# sqrwear2_0.net
KiCad netlist of a schematic drawn in EAGLE
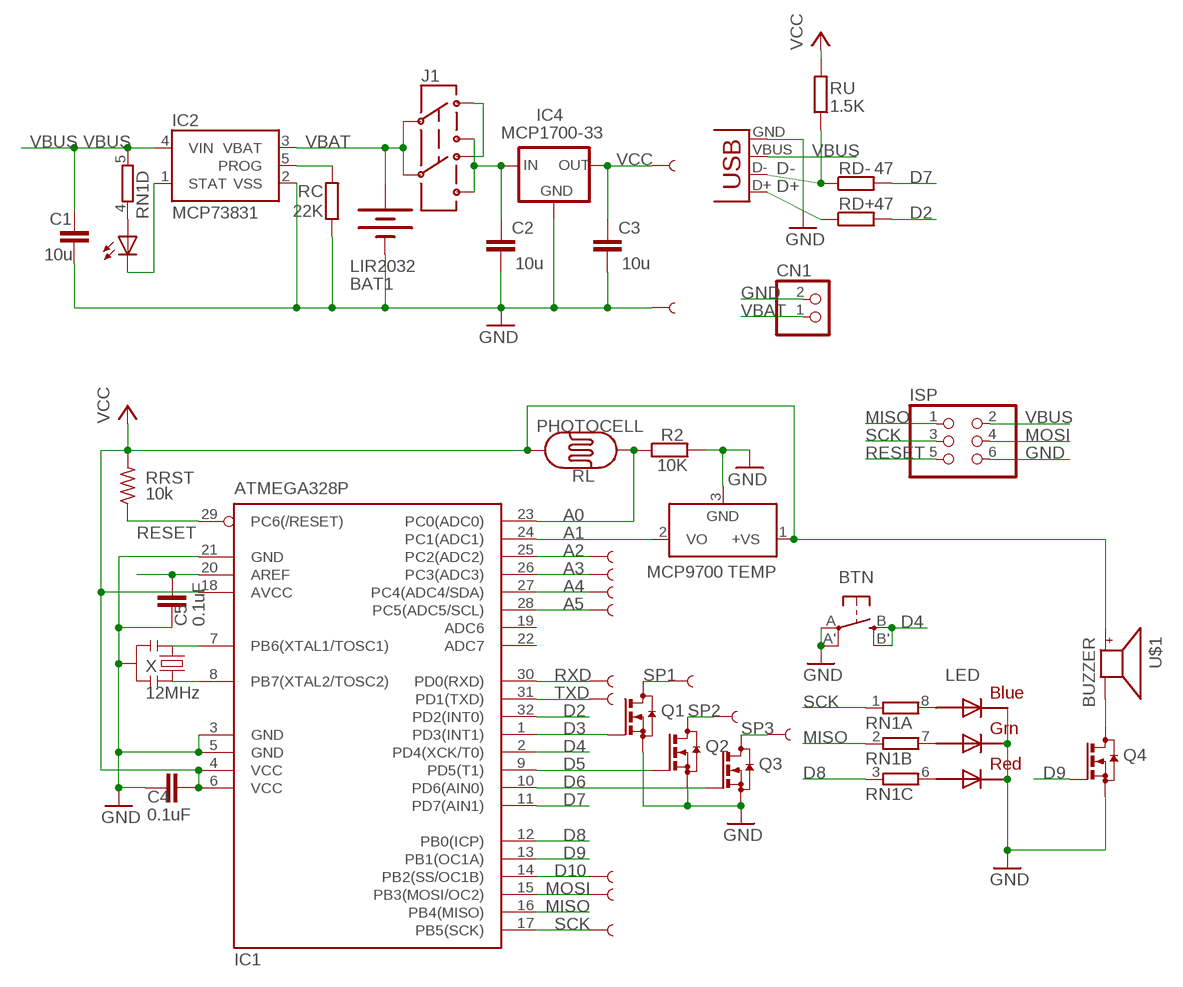
[diagram p0: schematic, sheet 1]

(export (version "E")
  (design (tool "Eeschema 10.0.6"))
  (components
    (comp (ref "BAT1")
      (value "LIR2032")
      (footprint "eagle-import:BATTCOM_20MM_PTH_SMT")
      (libsource (lib "eagle-import") (part "BATTERYBATTCOM_20MM_PTH_SMT"))
    )
    (comp (ref "BTN")
      (value "EVQQ2")
      (footprint "eagle-import:EVQ-Q2")
      (libsource (lib "eagle-import") (part "EVQQ2"))
    )
    (comp (ref "C1")
      (value "10u")
      (footprint "eagle-import:C0805")
      (libsource (lib "eagle-import") (part "resistor_C-EUC0805"))
    )
    (comp (ref "C2")
      (value "10u")
      (footprint "eagle-import:C0805")
      (libsource (lib "eagle-import") (part "resistor_C-EUC0805"))
    )
    (comp (ref "C3")
      (value "10u")
      (footprint "eagle-import:C0805")
      (libsource (lib "eagle-import") (part "resistor_C-EUC0805"))
    )
    (comp (ref "C4")
      (value "0.1uF")
      (footprint "eagle-import:C0805")
      (libsource (lib "eagle-import") (part "C-EUC0805"))
    )
    (comp (ref "C5")
      (value "0.1uF")
      (footprint "eagle-import:C0805")
      (libsource (lib "eagle-import") (part "C-EUC0805"))
    )
    (comp (ref "CHG")
      (value "0805")
      (footprint "eagle-import:CHIPLED_0805")
      (libsource (lib "eagle-import") (part "LEDCHIPLED_0805"))
    )
    (comp (ref "CN1")
      (value "JST_2PIN-SMT-RA")
      (footprint "eagle-import:JST-PH-2-SMT-RA")
      (libsource (lib "eagle-import") (part "JST_2PIN-SMT-RA"))
    )
    (comp (ref "IC1")
      (value "ATMEGA328P")
      (footprint "eagle-import:TQFP32-08")
      (fields (field (name "MPN") "ATMEGA8-16AU"))
      (libsource (lib "eagle-import") (part "MEGA8-AI"))
    )
    (comp (ref "IC2")
      (value "MCP73831")
      (footprint "eagle-import:SOT23-5")
      (libsource (lib "eagle-import") (part "MCP73831"))
    )
    (comp (ref "IC4")
      (value "MCP1700-33")
      (footprint "eagle-import:SOT23")
      (libsource (lib "eagle-import") (part "MCP1700SOT233"))
    )
    (comp (ref "ISP")
      (value "PINHD-2X3")
      (footprint "eagle-import:2X03")
      (libsource (lib "eagle-import") (part "PINHD-2X3"))
    )
    (comp (ref "J1")
      (value "AYZ0202")
      (footprint "eagle-import:AYZ0202")
      (libsource (lib "eagle-import") (part "AYZ0202"))
    )
    (comp (ref "LED")
      (value "RGBLED5050")
      (footprint "eagle-import:RGBLED5050")
      (libsource (lib "eagle-import") (part "RGBLED5050"))
    )
    (comp (ref "PAD_3")
      (value "SEWTAP6")
      (footprint "eagle-import:PETAL-SMALL-2SIDE11")
      (libsource (lib "eagle-import") (part "SEWTAP611"))
    )
    (comp (ref "PAD_5")
      (value "SEWTAP6")
      (footprint "eagle-import:PETAL-SMALL-2SIDE1")
      (libsource (lib "eagle-import") (part "SEWTAP61"))
    )
    (comp (ref "PAD_6")
      (value "SEWTAP6")
      (footprint "eagle-import:PETAL-SMALL-2SIDE1")
      (libsource (lib "eagle-import") (part "SEWTAP61"))
    )
    (comp (ref "PAD_10")
      (value "SEWTAP6")
      (footprint "eagle-import:PETAL-SMALL-2SIDE11")
      (libsource (lib "eagle-import") (part "SEWTAP611"))
    )
    (comp (ref "PAD_11")
      (value "SEWTAP6")
      (footprint "eagle-import:PETAL-SMALL-2SIDE1")
      (libsource (lib "eagle-import") (part "SEWTAP61"))
    )
    (comp (ref "PAD_13")
      (value "SEWTAP6")
      (footprint "eagle-import:PETAL-SMALL-2SIDE1")
      (libsource (lib "eagle-import") (part "SEWTAP61"))
    )
    (comp (ref "PAD_A2")
      (value "SEWTAP6")
      (footprint "eagle-import:PETAL-SMALL-2SIDE1")
      (libsource (lib "eagle-import") (part "SEWTAP61"))
    )
    (comp (ref "PAD_A3")
      (value "SEWTAP6")
      (footprint "eagle-import:PETAL-SMALL-2SIDE1")
      (libsource (lib "eagle-import") (part "SEWTAP61"))
    )
    (comp (ref "PAD_A4")
      (value "SEWTAP6")
      (footprint "eagle-import:PETAL-SMALL-2SIDE11")
      (libsource (lib "eagle-import") (part "SEWTAP611"))
    )
    (comp (ref "PAD_A5")
      (value "SEWTAP6")
      (footprint "eagle-import:PETAL-SMALL-2SIDE11")
      (libsource (lib "eagle-import") (part "SEWTAP611"))
    )
    (comp (ref "PAD_GND")
      (value "SEWTAP6")
      (footprint "eagle-import:PETAL-SMALL-2SIDE11")
      (libsource (lib "eagle-import") (part "SEWTAP611"))
    )
    (comp (ref "PAD_RXD")
      (value "SEWTAP61")
      (footprint "eagle-import:PETAL-SMALL-2SIDE1")
      (libsource (lib "eagle-import") (part "SEWTAP61"))
    )
    (comp (ref "PAD_TXD")
      (value "SEWTAP6")
      (footprint "eagle-import:PETAL-SMALL-2SIDE1")
      (libsource (lib "eagle-import") (part "SEWTAP61"))
    )
    (comp (ref "PAD_VCC")
      (value "SEWTAP6")
      (footprint "eagle-import:PETAL-SMALL-2SIDE11")
      (libsource (lib "eagle-import") (part "SEWTAP611"))
    )
    (comp (ref "Q1")
      (value "BSS123")
      (footprint "eagle-import:SOT23")
      (libsource (lib "eagle-import") (part "BSS123"))
    )
    (comp (ref "Q2")
      (value "BSS123")
      (footprint "eagle-import:SOT23")
      (libsource (lib "eagle-import") (part "BSS123"))
    )
    (comp (ref "Q3")
      (value "BSS123")
      (footprint "eagle-import:SOT23")
      (libsource (lib "eagle-import") (part "BSS123"))
    )
    (comp (ref "Q4")
      (value "BSS123")
      (footprint "eagle-import:SOT23")
      (libsource (lib "eagle-import") (part "BSS123"))
    )
    (comp (ref "R2")
      (value "10K")
      (footprint "eagle-import:R0805")
      (libsource (lib "eagle-import") (part "R-EU_R0805"))
    )
    (comp (ref "RC")
      (value "22K")
      (footprint "eagle-import:R0805")
      (libsource (lib "eagle-import") (part "R-EU_R0805"))
    )
    (comp (ref "RD+")
      (value "47")
      (footprint "eagle-import:R0805")
      (libsource (lib "eagle-import") (part "R-EU_R0805"))
    )
    (comp (ref "RD-")
      (value "47")
      (footprint "eagle-import:R0805")
      (libsource (lib "eagle-import") (part "R-EU_R0805"))
    )
    (comp (ref "RL")
      (value "PHOTOCELL")
      (footprint "eagle-import:PHOTOCELL")
      (libsource (lib "eagle-import") (part "PHOTOCELLPTH"))
    )
    (comp (ref "RN1")
      (value "4R-NEXB38V")
      (footprint "eagle-import:EXB38V")
      (libsource (lib "eagle-import") (part "4R-NEXB38V"))
    )
    (comp (ref "RRST")
      (value "10k")
      (footprint "eagle-import:R0805@1")
      (libsource (lib "eagle-import") (part "R-US_R0805"))
    )
    (comp (ref "RU")
      (value "1.5K")
      (footprint "eagle-import:R0805")
      (libsource (lib "eagle-import") (part "R-EU_R0805"))
    )
    (comp (ref "TEMP")
      (value "MCP9700")
      (footprint "eagle-import:SOT23")
      (libsource (lib "eagle-import") (part "LM50"))
    )
    (comp (ref "U$1")
      (value "BUZZER")
      (footprint "eagle-import:SMT-8585-BUZZER")
      (libsource (lib "eagle-import") (part "BUZZER"))
    )
    (comp (ref "X")
      (value "12MHz")
      (footprint "eagle-import:RESONATOR-SMD")
      (libsource (lib "eagle-import") (part "RESONATORSMD"))
    )
    (comp (ref "X1")
      (value "USBSMD")
      (footprint "eagle-import:USB-MINIB")
      (libsource (lib "eagle-import") (part "USBSMD"))
    )
  )
  (nets
    (net (code "1") (name "/A0") (class "Default")
      (node (ref "IC1") (pin "23") (pinfunction "PC0(ADC0)_23") (pintype "bidirectional"))
      (node (ref "R2") (pin "1") (pinfunction "1_1") (pintype "passive"))
      (node (ref "RL") (pin "1") (pinfunction "P$1_1") (pintype "bidirectional"))
    )
    (net (code "2") (name "/A1") (class "Default")
      (node (ref "IC1") (pin "24") (pinfunction "PC1(ADC1)_24") (pintype "bidirectional"))
      (node (ref "TEMP") (pin "2") (pinfunction "VO_2") (pintype "input"))
    )
    (net (code "3") (name "/A2") (class "Default")
      (node (ref "IC1") (pin "25") (pinfunction "PC2(ADC2)_25") (pintype "bidirectional"))
      (node (ref "PAD_A2") (pin "1") (pinfunction "1_1") (pintype "bidirectional"))
    )
    (net (code "4") (name "/A3") (class "Default")
      (node (ref "IC1") (pin "26") (pinfunction "PC3(ADC3)_26") (pintype "bidirectional"))
      (node (ref "PAD_A3") (pin "1") (pinfunction "1_1") (pintype "bidirectional"))
    )
    (net (code "5") (name "/A4") (class "Default")
      (node (ref "IC1") (pin "27") (pinfunction "PC4(ADC4/SDA)_27") (pintype "bidirectional"))
      (node (ref "PAD_A4") (pin "1") (pinfunction "1_1") (pintype "bidirectional"))
    )
    (net (code "6") (name "/A5") (class "Default")
      (node (ref "IC1") (pin "28") (pinfunction "PC5(ADC5/SCL)_28") (pintype "bidirectional"))
      (node (ref "PAD_A5") (pin "1") (pinfunction "1_1") (pintype "bidirectional"))
    )
    (net (code "7") (name "/D+") (class "Default")
      (node (ref "RD+") (pin "1") (pinfunction "1_1") (pintype "passive"))
      (node (ref "X1") (pin "D+") (pinfunction "D+_D+") (pintype "bidirectional"))
    )
    (net (code "8") (name "/D-") (class "Default")
      (node (ref "RD-") (pin "1") (pinfunction "1_1") (pintype "passive"))
      (node (ref "RU") (pin "1") (pinfunction "1_1") (pintype "passive"))
      (node (ref "X1") (pin "D-") (pinfunction "D-_D-") (pintype "bidirectional"))
    )
    (net (code "9") (name "/D2") (class "Default")
      (node (ref "IC1") (pin "32") (pinfunction "PD2(INT0)_32") (pintype "bidirectional"))
      (node (ref "RD+") (pin "2") (pinfunction "2_2") (pintype "passive"))
    )
    (net (code "10") (name "/D3") (class "Default")
      (node (ref "IC1") (pin "1") (pinfunction "PD3(INT1)_1") (pintype "bidirectional"))
      (node (ref "Q1") (pin "1") (pinfunction "G_1") (pintype "passive"))
    )
    (net (code "11") (name "/D4") (class "Default")
      (node (ref "BTN") (pin "B") (pinfunction "S_B") (pintype "passive"))
      (node (ref "BTN") (pin "B'") (pinfunction "S1_B'") (pintype "passive"))
      (node (ref "IC1") (pin "2") (pinfunction "PD4(XCK/T0)_2") (pintype "bidirectional"))
    )
    (net (code "12") (name "/D5") (class "Default")
      (node (ref "IC1") (pin "9") (pinfunction "PD5(T1)_9") (pintype "bidirectional"))
      (node (ref "Q2") (pin "1") (pinfunction "G_1") (pintype "passive"))
    )
    (net (code "13") (name "/D6") (class "Default")
      (node (ref "IC1") (pin "10") (pinfunction "PD6(AIN0)_10") (pintype "bidirectional"))
      (node (ref "Q3") (pin "1") (pinfunction "G_1") (pintype "passive"))
    )
    (net (code "14") (name "/D7") (class "Default")
      (node (ref "IC1") (pin "11") (pinfunction "PD7(AIN1)_11") (pintype "bidirectional"))
      (node (ref "RD-") (pin "2") (pinfunction "2_2") (pintype "passive"))
    )
    (net (code "15") (name "/D8") (class "Default")
      (node (ref "IC1") (pin "12") (pinfunction "PB0(ICP)_12") (pintype "bidirectional"))
      (node (ref "RN1") (pin "3") (pinfunction "1_3") (pintype "passive"))
    )
    (net (code "16") (name "/D9") (class "Default")
      (node (ref "IC1") (pin "13") (pinfunction "PB1(OC1A)_13") (pintype "bidirectional"))
      (node (ref "Q4") (pin "1") (pinfunction "G_1") (pintype "passive"))
    )
    (net (code "17") (name "/D10") (class "Default")
      (node (ref "IC1") (pin "14") (pinfunction "PB2(SS/OC1B)_14") (pintype "bidirectional"))
      (node (ref "PAD_10") (pin "1") (pinfunction "1_1") (pintype "bidirectional"))
    )
    (net (code "18") (name "/MISO") (class "Default")
      (node (ref "IC1") (pin "16") (pinfunction "PB4(MISO)_16") (pintype "bidirectional"))
      (node (ref "ISP") (pin "1") (pinfunction "1_1") (pintype "passive"))
      (node (ref "RN1") (pin "2") (pinfunction "1_2") (pintype "passive"))
    )
    (net (code "19") (name "/MOSI") (class "Default")
      (node (ref "IC1") (pin "15") (pinfunction "PB3(MOSI/OC2)_15") (pintype "bidirectional"))
      (node (ref "ISP") (pin "4") (pinfunction "4_4") (pintype "passive"))
      (node (ref "PAD_11") (pin "1") (pinfunction "1_1") (pintype "bidirectional"))
    )
    (net (code "20") (name "/RESET") (class "Default")
      (node (ref "IC1") (pin "29") (pinfunction "PC6(/RESET)_29") (pintype "bidirectional"))
      (node (ref "ISP") (pin "5") (pinfunction "5_5") (pintype "passive"))
      (node (ref "RRST") (pin "1") (pinfunction "1_1") (pintype "passive"))
    )
    (net (code "21") (name "/RXD") (class "Default")
      (node (ref "IC1") (pin "30") (pinfunction "PD0(RXD)_30") (pintype "bidirectional"))
      (node (ref "PAD_RXD") (pin "1") (pinfunction "1_1") (pintype "bidirectional"))
    )
    (net (code "22") (name "/SCK") (class "Default")
      (node (ref "IC1") (pin "17") (pinfunction "PB5(SCK)_17") (pintype "bidirectional"))
      (node (ref "ISP") (pin "3") (pinfunction "3_3") (pintype "passive"))
      (node (ref "PAD_13") (pin "1") (pinfunction "1_1") (pintype "bidirectional"))
      (node (ref "RN1") (pin "1") (pinfunction "1_1") (pintype "passive"))
    )
    (net (code "23") (name "/SP1") (class "Default")
      (node (ref "PAD_3") (pin "1") (pinfunction "1_1") (pintype "bidirectional"))
      (node (ref "Q1") (pin "3") (pinfunction "D_3") (pintype "passive"))
    )
    (net (code "24") (name "/SP2") (class "Default")
      (node (ref "PAD_5") (pin "1") (pinfunction "1_1") (pintype "bidirectional"))
      (node (ref "Q2") (pin "3") (pinfunction "D_3") (pintype "passive"))
    )
    (net (code "25") (name "/SP3") (class "Default")
      (node (ref "PAD_6") (pin "1") (pinfunction "1_1") (pintype "bidirectional"))
      (node (ref "Q3") (pin "3") (pinfunction "D_3") (pintype "passive"))
    )
    (net (code "26") (name "/TXD") (class "Default")
      (node (ref "IC1") (pin "31") (pinfunction "PD1(TXD)_31") (pintype "bidirectional"))
      (node (ref "PAD_TXD") (pin "1") (pinfunction "1_1") (pintype "bidirectional"))
    )
    (net (code "27") (name "/VBAT") (class "Default")
      (node (ref "BAT1") (pin "P$2") (pinfunction "+_P$2") (pintype "power_in"))
      (node (ref "CN1") (pin "1") (pinfunction "2_1") (pintype "passive"))
      (node (ref "IC2") (pin "3") (pinfunction "VBAT_3") (pintype "power_in"))
      (node (ref "J1") (pin "2") (pinfunction "2_2") (pintype "bidirectional"))
      (node (ref "J1") (pin "5") (pinfunction "5_5") (pintype "bidirectional"))
    )
    (net (code "28") (name "/VBUS") (class "Default")
      (node (ref "C1") (pin "1") (pinfunction "1_1") (pintype "passive"))
      (node (ref "IC2") (pin "4") (pinfunction "VIN_4") (pintype "power_in"))
      (node (ref "ISP") (pin "2") (pinfunction "2_2") (pintype "passive"))
      (node (ref "RN1") (pin "5") (pinfunction "2_5") (pintype "passive"))
      (node (ref "X1") (pin "VBUS") (pinfunction "VBUS_VBUS") (pintype "bidirectional"))
    )
    (net (code "29") (name "GND") (class "Default")
      (node (ref "BAT1") (pin "P$1") (pinfunction "-_P$1") (pintype "power_in"))
      (node (ref "BTN") (pin "A") (pinfunction "P_A") (pintype "passive"))
      (node (ref "BTN") (pin "A'") (pinfunction "P1_A'") (pintype "passive"))
      (node (ref "C1") (pin "2") (pinfunction "2_2") (pintype "passive"))
      (node (ref "C2") (pin "2") (pinfunction "2_2") (pintype "passive"))
      (node (ref "C3") (pin "2") (pinfunction "2_2") (pintype "passive"))
      (node (ref "C4") (pin "1") (pinfunction "1_1") (pintype "passive"))
      (node (ref "C5") (pin "1") (pinfunction "1_1") (pintype "passive"))
      (node (ref "CN1") (pin "2") (pinfunction "1_2") (pintype "passive"))
      (node (ref "IC1") (pin "21") (pinfunction "GND_21") (pintype "power_in"))
      (node (ref "IC1") (pin "3") (pinfunction "GND_3") (pintype "power_in"))
      (node (ref "IC1") (pin "5") (pinfunction "GND_5") (pintype "power_in"))
      (node (ref "IC2") (pin "2") (pinfunction "VSS_2") (pintype "power_in"))
      (node (ref "IC4") (pin "1") (pinfunction "GND_1") (pintype "input"))
      (node (ref "ISP") (pin "6") (pinfunction "6_6") (pintype "passive"))
      (node (ref "LED") (pin "4") (pinfunction "BLUE_C_4") (pintype "bidirectional"))
      (node (ref "LED") (pin "5") (pinfunction "RED_C_5") (pintype "bidirectional"))
      (node (ref "LED") (pin "6") (pinfunction "GREEN_C_6") (pintype "bidirectional"))
      (node (ref "PAD_GND") (pin "1") (pinfunction "1_1") (pintype "bidirectional"))
      (node (ref "Q1") (pin "2") (pinfunction "S_2") (pintype "passive"))
      (node (ref "Q2") (pin "2") (pinfunction "S_2") (pintype "passive"))
      (node (ref "Q3") (pin "2") (pinfunction "S_2") (pintype "passive"))
      (node (ref "Q4") (pin "2") (pinfunction "S_2") (pintype "passive"))
      (node (ref "R2") (pin "2") (pinfunction "2_2") (pintype "passive"))
      (node (ref "RC") (pin "1") (pinfunction "1_1") (pintype "passive"))
      (node (ref "TEMP") (pin "3") (pinfunction "GND_3") (pintype "power_in"))
      (node (ref "X") (pin "2") (pinfunction "2_2") (pintype "passive"))
      (node (ref "X1") (pin "GND") (pinfunction "GND_GND") (pintype "bidirectional"))
    )
    (net (code "30") (name "Net-(IC1-AREF)") (class "Default")
      (node (ref "C5") (pin "2") (pinfunction "2_2") (pintype "passive"))
      (node (ref "IC1") (pin "20") (pinfunction "AREF_20") (pintype "passive"))
    )
    (net (code "31") (name "Net-(IC1-PB6(XTAL1{slash}TOSC1))") (class "Default")
      (node (ref "IC1") (pin "7") (pinfunction "PB6(XTAL1/TOSC1)_7") (pintype "bidirectional"))
      (node (ref "X") (pin "1") (pinfunction "1_1") (pintype "passive"))
    )
    (net (code "32") (name "Net-(IC1-PB7(XTAL2{slash}TOSC2))") (class "Default")
      (node (ref "IC1") (pin "8") (pinfunction "PB7(XTAL2/TOSC2)_8") (pintype "bidirectional"))
      (node (ref "X") (pin "3") (pinfunction "3_3") (pintype "passive"))
    )
    (net (code "33") (name "Net-(IC2-PROG)") (class "Default")
      (node (ref "IC2") (pin "5") (pinfunction "PROG_5") (pintype "input"))
      (node (ref "RC") (pin "2") (pinfunction "2_2") (pintype "passive"))
    )
    (net (code "34") (name "Net-(IC2-STAT)") (class "Default")
      (node (ref "CHG") (pin "C") (pinfunction "C_C") (pintype "passive"))
      (node (ref "IC2") (pin "1") (pinfunction "STAT_1") (pintype "output"))
    )
    (net (code "35") (name "Net-(IC4-IN)") (class "Default")
      (node (ref "C2") (pin "1") (pinfunction "1_1") (pintype "passive"))
      (node (ref "IC4") (pin "3") (pinfunction "IN_3") (pintype "input"))
      (node (ref "J1") (pin "1") (pinfunction "3_1") (pintype "bidirectional"))
      (node (ref "J1") (pin "4") (pinfunction "6_4") (pintype "bidirectional"))
    )
    (net (code "36") (name "Net-(J1-1)") (class "Default")
      (node (ref "J1") (pin "3") (pinfunction "1_3") (pintype "bidirectional"))
      (node (ref "J1") (pin "6") (pinfunction "4_6") (pintype "bidirectional"))
    )
    (net (code "37") (name "Net-(LED-BLUE_A)") (class "Default")
      (node (ref "LED") (pin "3") (pinfunction "BLUE_A_3") (pintype "bidirectional"))
      (node (ref "RN1") (pin "8") (pinfunction "2_8") (pintype "passive"))
    )
    (net (code "38") (name "Net-(LED-GREEN_A)") (class "Default")
      (node (ref "LED") (pin "1") (pinfunction "GREEN_A_1") (pintype "bidirectional"))
      (node (ref "RN1") (pin "7") (pinfunction "2_7") (pintype "passive"))
    )
    (net (code "39") (name "Net-(LED-RED_A)") (class "Default")
      (node (ref "LED") (pin "2") (pinfunction "RED_A_2") (pintype "bidirectional"))
      (node (ref "RN1") (pin "6") (pinfunction "2_6") (pintype "passive"))
    )
    (net (code "40") (name "Net-(Q4-D)") (class "Default")
      (node (ref "Q4") (pin "3") (pinfunction "D_3") (pintype "passive"))
      (node (ref "U$1") (pin "-") (pinfunction "-_-") (pintype "passive"))
    )
    (net (code "41") (name "Net-(RN1D-1)") (class "Default")
      (node (ref "CHG") (pin "A") (pinfunction "A_A") (pintype "passive"))
      (node (ref "RN1") (pin "4") (pinfunction "1_4") (pintype "passive"))
    )
    (net (code "42") (name "VCC") (class "Default")
      (node (ref "C3") (pin "1") (pinfunction "1_1") (pintype "passive"))
      (node (ref "C4") (pin "2") (pinfunction "2_2") (pintype "passive"))
      (node (ref "IC1") (pin "18") (pinfunction "AVCC_18") (pintype "power_in"))
      (node (ref "IC1") (pin "4") (pinfunction "VCC_4") (pintype "power_in"))
      (node (ref "IC1") (pin "6") (pinfunction "VCC_6") (pintype "power_in"))
      (node (ref "IC4") (pin "2") (pinfunction "OUT_2") (pintype "passive"))
      (node (ref "PAD_VCC") (pin "1") (pinfunction "1_1") (pintype "bidirectional"))
      (node (ref "RL") (pin "2") (pinfunction "P$2_2") (pintype "bidirectional"))
      (node (ref "RRST") (pin "2") (pinfunction "2_2") (pintype "passive"))
      (node (ref "RU") (pin "2") (pinfunction "2_2") (pintype "passive"))
      (node (ref "TEMP") (pin "1") (pinfunction "+VS_1") (pintype "input"))
      (node (ref "U$1") (pin "+") (pinfunction "+_+") (pintype "passive"))
    )
    (net (code "43") (name "unconnected-(IC1-ADC6-Pad19)") (class "Default")
      (node (ref "IC1") (pin "19") (pinfunction "ADC6_19") (pintype "bidirectional"))
    )
    (net (code "44") (name "unconnected-(IC1-ADC7-Pad22)") (class "Default")
      (node (ref "IC1") (pin "22") (pinfunction "ADC7_22") (pintype "bidirectional"))
    )
  )
)
